# moana-lf-robot.net
KiCad netlist of a schematic drawn in EasyEDA
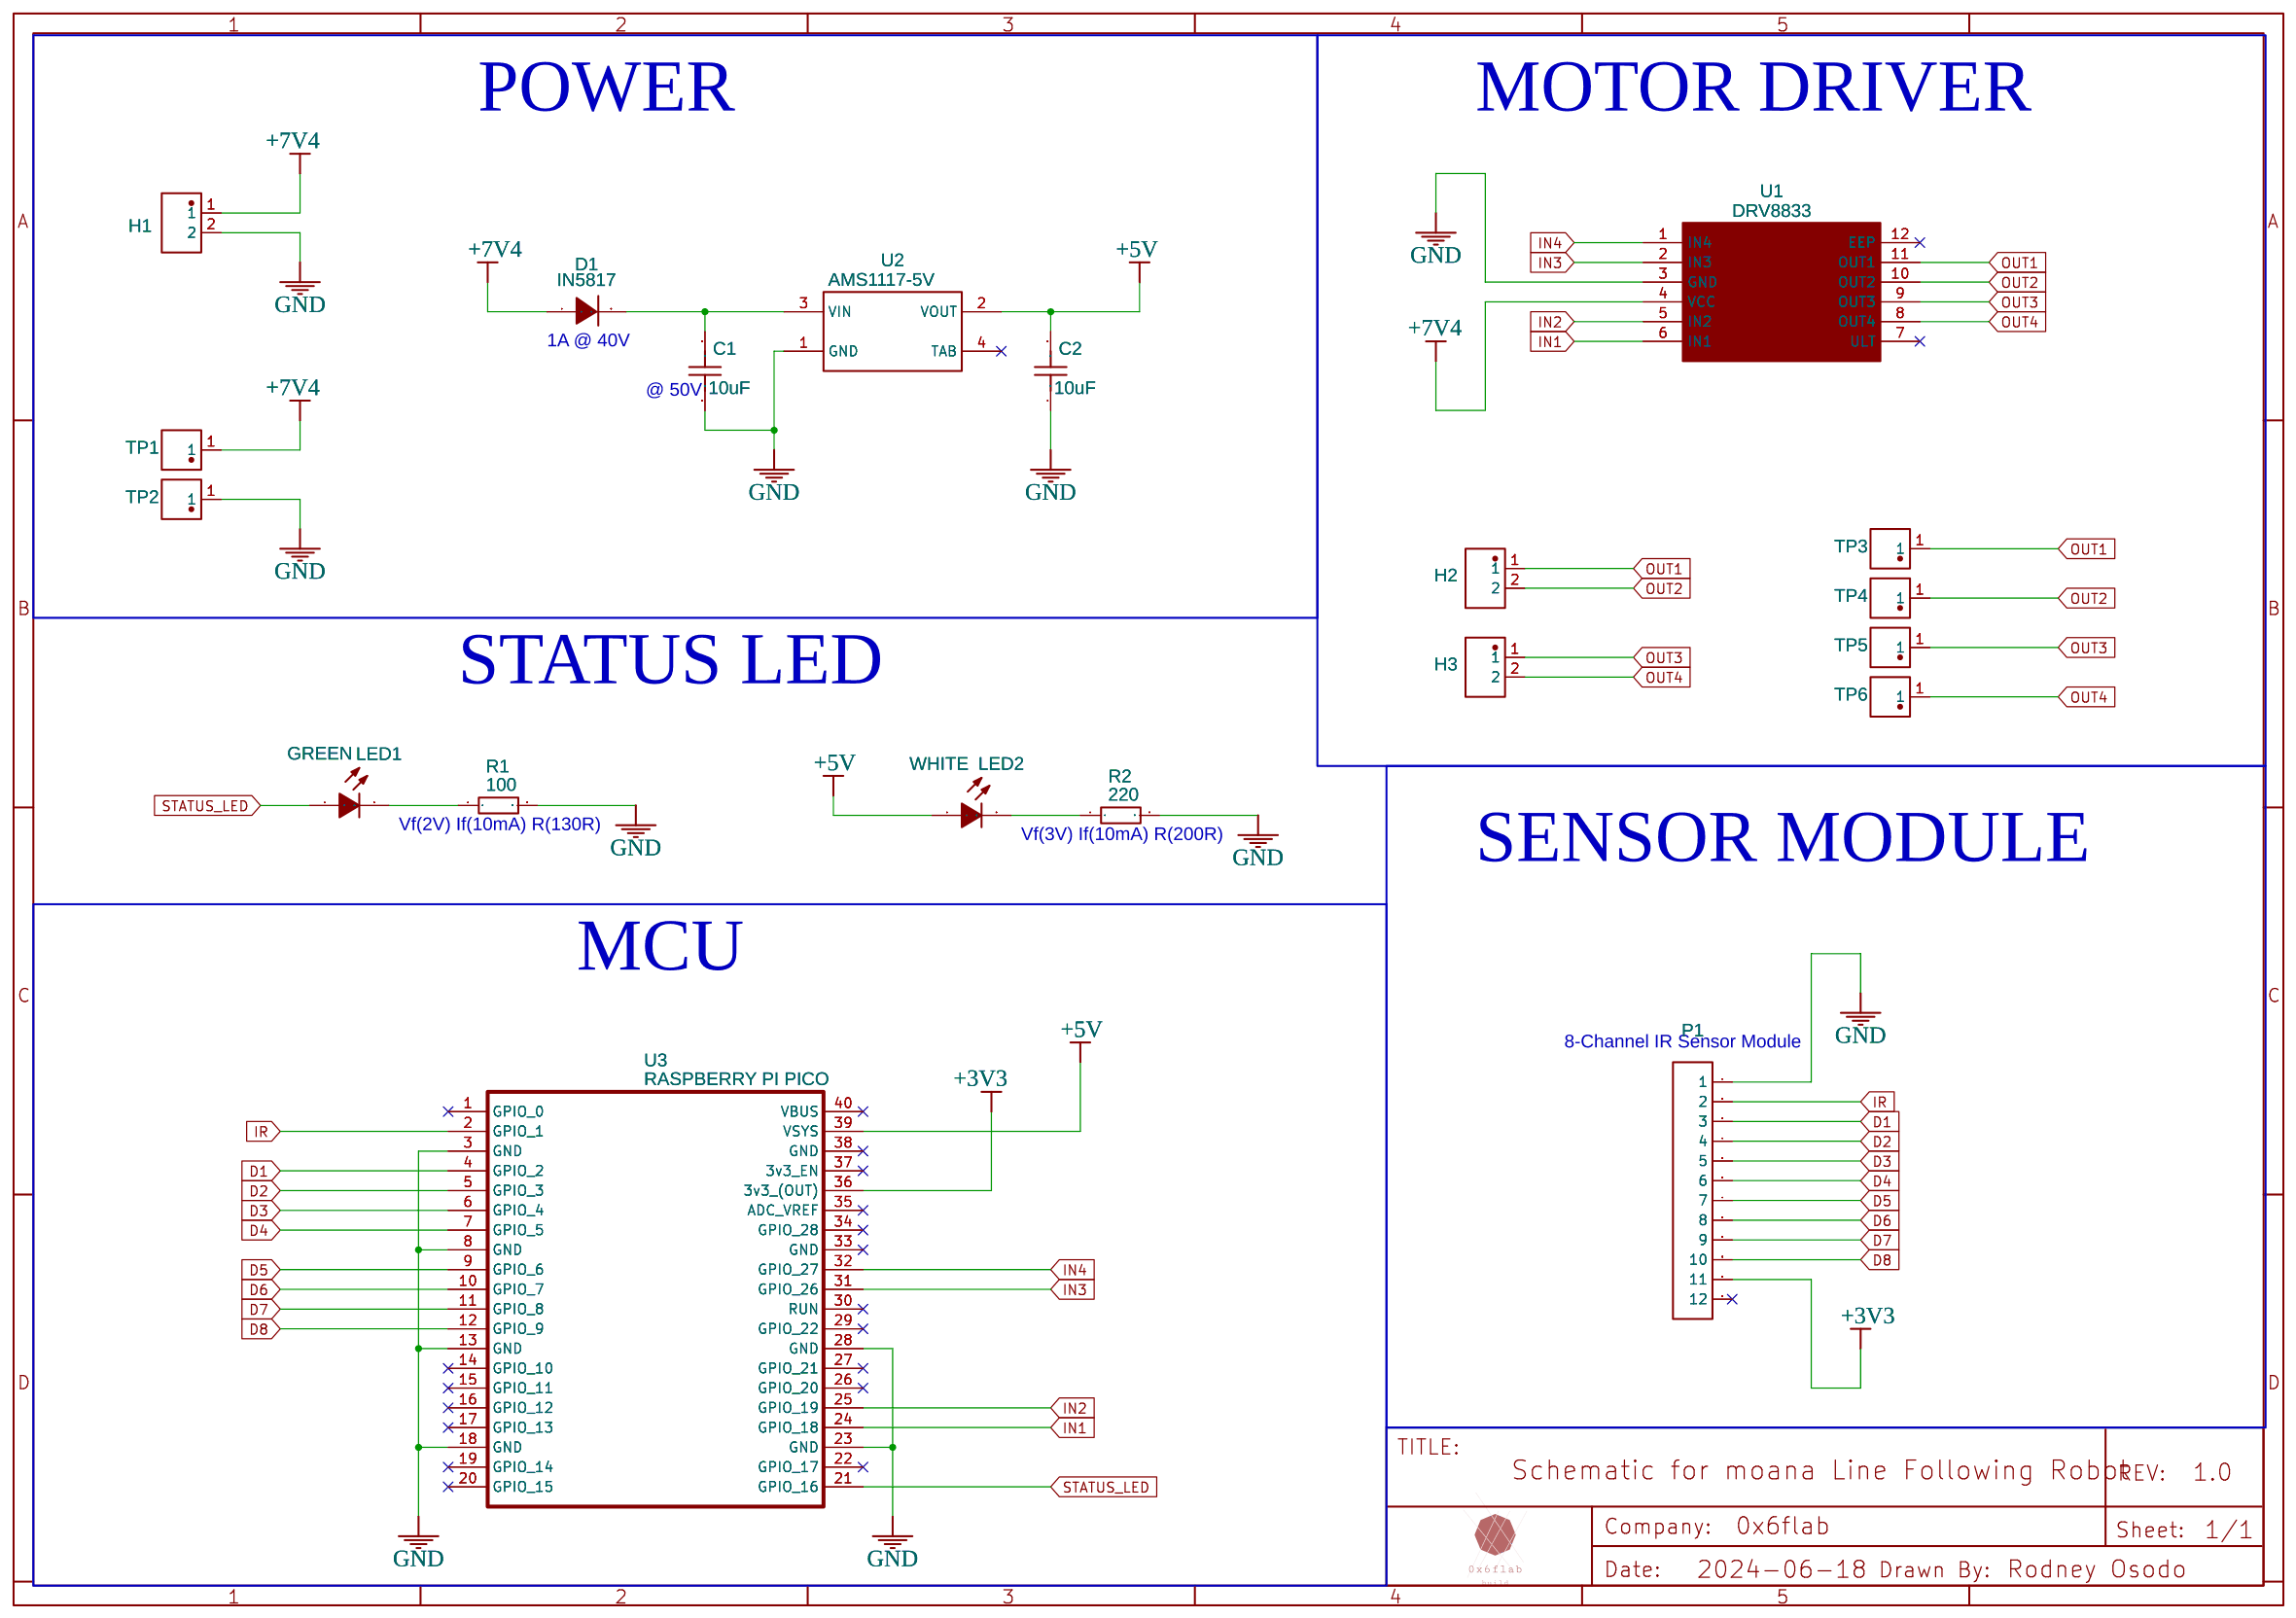
[diagram p0: schematic sheet]

(export (version "E")
  (design (tool "Eeschema 10.0.6"))
  (components
    (comp (ref "C1")
      (value "10uF")
      (fields
        (field (name "Manufacturer Part") "CC1H104ZC14D3F5O10MF")
        (field (name "Manufacturer") "Dersonic(德尔创)")
      )
      (libsource (lib "") (part "CC1H104ZC14D3F5O10MF"))
    )
    (comp (ref "C2")
      (value "10uF")
      (fields
        (field (name "Manufacturer Part") "CC1H104ZC14D3F5O10MF")
        (field (name "Manufacturer") "Dersonic(德尔创)")
      )
      (libsource (lib "") (part "CC1H104ZC14D3F5O10MF"))
    )
    (comp (ref "D1")
      (value "IN5817")
      (fields (field (name "Manufacturer Part") "1N5817") (field (name "Manufacturer") "STMicroelectronics"))
      (libsource (lib "") (part "IN5817 SCHOTTKY DIODE"))
    )
    (comp (ref "H1")
      (value "210-91-02GB01")
      (fields (field (name "Manufacturer") "PINREX(频锐科技)"))
      (libsource (lib "") (part "210-91-02GB01"))
    )
    (comp (ref "H2")
      (value "210-91-02GB01")
      (fields (field (name "Manufacturer") "PINREX(频锐科技)"))
      (libsource (lib "") (part "210-91-02GB01"))
    )
    (comp (ref "H3")
      (value "210-91-02GB01")
      (fields (field (name "Manufacturer") "PINREX(频锐科技)"))
      (libsource (lib "") (part "210-91-02GB01"))
    )
    (comp (ref "LED1")
      (value "GREEN")
      (fields
        (field (name "Manufacturer Part") "204-10SUBC/C470/S400-A4")
        (field (name "Manufacturer") "EVERLIGHT(亿光)")
      )
      (libsource (lib "") (part "204-10SUBC/C470/S400-A4"))
    )
    (comp (ref "LED2")
      (value "WHITE")
      (fields
        (field (name "Manufacturer Part") "204-10SUBC/C470/S400-A4")
        (field (name "Manufacturer") "EVERLIGHT(亿光)")
      )
      (libsource (lib "") (part "204-10SUBC/C470/S400-A4"))
    )
    (comp (ref "P1")
      (value "HEADER - 2.54MM 1X12")
      (fields (field (name "Manufacturer Part") "2.54_1x12") (field (name "Manufacturer") "ReliaPro"))
      (libsource (lib "") (part "HEADER - 2.54MM 1X12"))
    )
    (comp (ref "R1")
      (value "100")
      (fields (field (name "Manufacturer") "Chian Chia Elec"))
      (libsource (lib "") (part "MF1/4W-1Ω±1% T52"))
    )
    (comp (ref "R2")
      (value "220")
      (fields (field (name "Manufacturer") "Chian Chia Elec"))
      (libsource (lib "") (part "MF1/4W-1Ω±1% T52"))
    )
    (comp (ref "TP1")
      (value "TP_SMD_2.5mm")
      (fields (field (name "Manufacturer Part") "15X5焊片"))
      (libsource (lib "") (part "TP_SMD_2.5mm"))
    )
    (comp (ref "TP2")
      (value "TP_SMD_2.5mm")
      (fields (field (name "Manufacturer Part") "15X5焊片"))
      (libsource (lib "") (part "TP_SMD_2.5mm"))
    )
    (comp (ref "TP3")
      (value "TP_SMD_2.5mm")
      (fields (field (name "Manufacturer Part") "15X5焊片"))
      (libsource (lib "") (part "TP_SMD_2.5mm"))
    )
    (comp (ref "TP4")
      (value "TP_SMD_2.5mm")
      (fields (field (name "Manufacturer Part") "15X5焊片"))
      (libsource (lib "") (part "TP_SMD_2.5mm"))
    )
    (comp (ref "TP5")
      (value "TP_SMD_2.5mm")
      (fields (field (name "Manufacturer Part") "15X5焊片"))
      (libsource (lib "") (part "TP_SMD_2.5mm"))
    )
    (comp (ref "TP6")
      (value "TP_SMD_2.5mm")
      (fields (field (name "Manufacturer Part") "15X5焊片"))
      (libsource (lib "") (part "TP_SMD_2.5mm"))
    )
    (comp (ref "U1") (value "DRV8833") (libsource (lib "") (part "DRV8833")))
    (comp (ref "U2")
      (value "AMS1117-5V")
      (fields (field (name "Manufacturer") "WPMtek(维攀微)"))
      (libsource (lib "") (part "AMS1117-5V"))
    )
    (comp (ref "U3") (value "RASPBERRY PI PICO") (libsource (lib "") (part "RASPBERRY PI PICO")))
  )
  (nets
    (net (code "1") (name "+3V3") (class "Default")
      (node (ref "P1") (pin "11") (pinfunction "11_11") (pintype "input"))
      (node (ref "U3") (pin "36") (pinfunction "3v3_(OUT)_36") (pintype "unspecified"))
    )
    (net (code "2") (name "+5V") (class "Default")
      (node (ref "C2") (pin "2") (pinfunction "2_2") (pintype "unspecified"))
      (node (ref "LED2") (pin "1") (pinfunction "A_1") (pintype "input"))
      (node (ref "U2") (pin "2") (pinfunction "VOUT_2") (pintype "unspecified"))
      (node (ref "U3") (pin "39") (pinfunction "VSYS_39") (pintype "unspecified"))
    )
    (net (code "3") (name "+7V4") (class "Default")
      (node (ref "D1") (pin "1") (pinfunction "A_1") (pintype "unspecified"))
      (node (ref "H1") (pin "1") (pinfunction "1_1") (pintype "unspecified"))
      (node (ref "TP1") (pin "1") (pinfunction "1_1") (pintype "unspecified"))
      (node (ref "U1") (pin "4") (pinfunction "VCC_4") (pintype "unspecified"))
    )
    (net (code "4") (name "D1") (class "Default")
      (node (ref "P1") (pin "3") (pinfunction "3_3") (pintype "input"))
      (node (ref "U3") (pin "4") (pinfunction "GPIO_2_4") (pintype "unspecified"))
    )
    (net (code "5") (name "D2") (class "Default")
      (node (ref "P1") (pin "4") (pinfunction "4_4") (pintype "input"))
      (node (ref "U3") (pin "5") (pinfunction "GPIO_3_5") (pintype "unspecified"))
    )
    (net (code "6") (name "D3") (class "Default")
      (node (ref "P1") (pin "5") (pinfunction "5_5") (pintype "input"))
      (node (ref "U3") (pin "6") (pinfunction "GPIO_4_6") (pintype "unspecified"))
    )
    (net (code "7") (name "D4") (class "Default")
      (node (ref "P1") (pin "6") (pinfunction "6_6") (pintype "input"))
      (node (ref "U3") (pin "7") (pinfunction "GPIO_5_7") (pintype "unspecified"))
    )
    (net (code "8") (name "D5") (class "Default")
      (node (ref "P1") (pin "7") (pinfunction "7_7") (pintype "input"))
      (node (ref "U3") (pin "9") (pinfunction "GPIO_6_9") (pintype "unspecified"))
    )
    (net (code "9") (name "D6") (class "Default")
      (node (ref "P1") (pin "8") (pinfunction "8_8") (pintype "input"))
      (node (ref "U3") (pin "10") (pinfunction "GPIO_7_10") (pintype "unspecified"))
    )
    (net (code "10") (name "D7") (class "Default")
      (node (ref "P1") (pin "9") (pinfunction "9_9") (pintype "input"))
      (node (ref "U3") (pin "11") (pinfunction "GPIO_8_11") (pintype "unspecified"))
    )
    (net (code "11") (name "D8") (class "Default")
      (node (ref "P1") (pin "10") (pinfunction "10_10") (pintype "input"))
      (node (ref "U3") (pin "12") (pinfunction "GPIO_9_12") (pintype "unspecified"))
    )
    (net (code "12") (name "GND") (class "Default")
      (node (ref "C1") (pin "1") (pinfunction "1_1") (pintype "unspecified"))
      (node (ref "C2") (pin "1") (pinfunction "1_1") (pintype "unspecified"))
      (node (ref "H1") (pin "2") (pinfunction "2_2") (pintype "unspecified"))
      (node (ref "P1") (pin "1") (pinfunction "1_1") (pintype "input"))
      (node (ref "R1") (pin "2") (pinfunction "2_2") (pintype "unspecified"))
      (node (ref "R2") (pin "2") (pinfunction "2_2") (pintype "unspecified"))
      (node (ref "TP2") (pin "1") (pinfunction "1_1") (pintype "unspecified"))
      (node (ref "U1") (pin "3") (pinfunction "GND_3") (pintype "unspecified"))
      (node (ref "U2") (pin "1") (pinfunction "GND_1") (pintype "unspecified"))
      (node (ref "U3") (pin "13") (pinfunction "GND_13") (pintype "unspecified"))
      (node (ref "U3") (pin "18") (pinfunction "GND_18") (pintype "unspecified"))
      (node (ref "U3") (pin "23") (pinfunction "GND_23") (pintype "unspecified"))
      (node (ref "U3") (pin "28") (pinfunction "GND_28") (pintype "unspecified"))
      (node (ref "U3") (pin "3") (pinfunction "GND_3") (pintype "unspecified"))
      (node (ref "U3") (pin "8") (pinfunction "GND_8") (pintype "unspecified"))
    )
    (net (code "13") (name "IN1") (class "Default")
      (node (ref "U1") (pin "6") (pinfunction "IN1_6") (pintype "unspecified"))
      (node (ref "U3") (pin "24") (pinfunction "GPIO_18_24") (pintype "unspecified"))
    )
    (net (code "14") (name "IN2") (class "Default")
      (node (ref "U1") (pin "5") (pinfunction "IN2_5") (pintype "unspecified"))
      (node (ref "U3") (pin "25") (pinfunction "GPIO_19_25") (pintype "unspecified"))
    )
    (net (code "15") (name "IN3") (class "Default")
      (node (ref "U1") (pin "2") (pinfunction "IN3_2") (pintype "unspecified"))
      (node (ref "U3") (pin "31") (pinfunction "GPIO_26_31") (pintype "unspecified"))
    )
    (net (code "16") (name "IN4") (class "Default")
      (node (ref "U1") (pin "1") (pinfunction "IN4_1") (pintype "unspecified"))
      (node (ref "U3") (pin "32") (pinfunction "GPIO_27_32") (pintype "unspecified"))
    )
    (net (code "17") (name "IR") (class "Default")
      (node (ref "P1") (pin "2") (pinfunction "2_2") (pintype "input"))
      (node (ref "U3") (pin "2") (pinfunction "GPIO_1_2") (pintype "unspecified"))
    )
    (net (code "18") (name "Net-(D1-K)") (class "Default")
      (node (ref "C1") (pin "2") (pinfunction "2_2") (pintype "unspecified"))
      (node (ref "D1") (pin "2") (pinfunction "K_2") (pintype "unspecified"))
      (node (ref "U2") (pin "3") (pinfunction "VIN_3") (pintype "unspecified"))
    )
    (net (code "19") (name "Net-(LED1-C)") (class "Default")
      (node (ref "LED1") (pin "2") (pinfunction "C_2") (pintype "input"))
      (node (ref "R1") (pin "1") (pinfunction "1_1") (pintype "unspecified"))
    )
    (net (code "20") (name "Net-(LED2-C)") (class "Default")
      (node (ref "LED2") (pin "2") (pinfunction "C_2") (pintype "input"))
      (node (ref "R2") (pin "1") (pinfunction "1_1") (pintype "unspecified"))
    )
    (net (code "21") (name "OUT1") (class "Default")
      (node (ref "H2") (pin "1") (pinfunction "1_1") (pintype "unspecified"))
      (node (ref "TP3") (pin "1") (pinfunction "1_1") (pintype "unspecified"))
      (node (ref "U1") (pin "11") (pinfunction "OUT1_11") (pintype "unspecified"))
    )
    (net (code "22") (name "OUT2") (class "Default")
      (node (ref "H2") (pin "2") (pinfunction "2_2") (pintype "unspecified"))
      (node (ref "TP4") (pin "1") (pinfunction "1_1") (pintype "unspecified"))
      (node (ref "U1") (pin "10") (pinfunction "OUT2_10") (pintype "unspecified"))
    )
    (net (code "23") (name "OUT3") (class "Default")
      (node (ref "H3") (pin "1") (pinfunction "1_1") (pintype "unspecified"))
      (node (ref "TP5") (pin "1") (pinfunction "1_1") (pintype "unspecified"))
      (node (ref "U1") (pin "9") (pinfunction "OUT3_9") (pintype "unspecified"))
    )
    (net (code "24") (name "OUT4") (class "Default")
      (node (ref "H3") (pin "2") (pinfunction "2_2") (pintype "unspecified"))
      (node (ref "TP6") (pin "1") (pinfunction "1_1") (pintype "unspecified"))
      (node (ref "U1") (pin "8") (pinfunction "OUT4_8") (pintype "unspecified"))
    )
    (net (code "25") (name "STATUS_LED") (class "Default")
      (node (ref "LED1") (pin "1") (pinfunction "A_1") (pintype "input"))
      (node (ref "U3") (pin "21") (pinfunction "GPIO_16_21") (pintype "unspecified"))
    )
    (net (code "26") (name "unconnected-(P1-Pad12)") (class "Default")
      (node (ref "P1") (pin "12") (pinfunction "12_12") (pintype "input+no_connect"))
    )
    (net (code "27") (name "unconnected-(U1-EEP-Pad12)") (class "Default")
      (node (ref "U1") (pin "12") (pinfunction "EEP_12") (pintype "unspecified+no_connect"))
    )
    (net (code "28") (name "unconnected-(U1-ULT-Pad7)") (class "Default")
      (node (ref "U1") (pin "7") (pinfunction "ULT_7") (pintype "unspecified+no_connect"))
    )
    (net (code "29") (name "unconnected-(U2-TAB-Pad4)") (class "Default")
      (node (ref "U2") (pin "4") (pinfunction "TAB_4") (pintype "unspecified+no_connect"))
    )
    (net (code "30") (name "unconnected-(U3-3v3_EN-Pad37)") (class "Default")
      (node (ref "U3") (pin "37") (pinfunction "3v3_EN_37") (pintype "unspecified+no_connect"))
    )
    (net (code "31") (name "unconnected-(U3-ADC_VREF-Pad35)") (class "Default")
      (node (ref "U3") (pin "35") (pinfunction "ADC_VREF_35") (pintype "unspecified+no_connect"))
    )
    (net (code "32") (name "unconnected-(U3-GND-Pad33)") (class "Default")
      (node (ref "U3") (pin "33") (pinfunction "GND_33") (pintype "unspecified+no_connect"))
    )
    (net (code "33") (name "unconnected-(U3-GND-Pad38)") (class "Default")
      (node (ref "U3") (pin "38") (pinfunction "GND_38") (pintype "unspecified+no_connect"))
    )
    (net (code "34") (name "unconnected-(U3-GPIO_0-Pad1)") (class "Default")
      (node (ref "U3") (pin "1") (pinfunction "GPIO_0_1") (pintype "unspecified+no_connect"))
    )
    (net (code "35") (name "unconnected-(U3-GPIO_10-Pad14)") (class "Default")
      (node (ref "U3") (pin "14") (pinfunction "GPIO_10_14") (pintype "unspecified+no_connect"))
    )
    (net (code "36") (name "unconnected-(U3-GPIO_11-Pad15)") (class "Default")
      (node (ref "U3") (pin "15") (pinfunction "GPIO_11_15") (pintype "unspecified+no_connect"))
    )
    (net (code "37") (name "unconnected-(U3-GPIO_12-Pad16)") (class "Default")
      (node (ref "U3") (pin "16") (pinfunction "GPIO_12_16") (pintype "unspecified+no_connect"))
    )
    (net (code "38") (name "unconnected-(U3-GPIO_13-Pad17)") (class "Default")
      (node (ref "U3") (pin "17") (pinfunction "GPIO_13_17") (pintype "unspecified+no_connect"))
    )
    (net (code "39") (name "unconnected-(U3-GPIO_14-Pad19)") (class "Default")
      (node (ref "U3") (pin "19") (pinfunction "GPIO_14_19") (pintype "unspecified+no_connect"))
    )
    (net (code "40") (name "unconnected-(U3-GPIO_15-Pad20)") (class "Default")
      (node (ref "U3") (pin "20") (pinfunction "GPIO_15_20") (pintype "unspecified+no_connect"))
    )
    (net (code "41") (name "unconnected-(U3-GPIO_17-Pad22)") (class "Default")
      (node (ref "U3") (pin "22") (pinfunction "GPIO_17_22") (pintype "unspecified+no_connect"))
    )
    (net (code "42") (name "unconnected-(U3-GPIO_20-Pad26)") (class "Default")
      (node (ref "U3") (pin "26") (pinfunction "GPIO_20_26") (pintype "unspecified+no_connect"))
    )
    (net (code "43") (name "unconnected-(U3-GPIO_21-Pad27)") (class "Default")
      (node (ref "U3") (pin "27") (pinfunction "GPIO_21_27") (pintype "unspecified+no_connect"))
    )
    (net (code "44") (name "unconnected-(U3-GPIO_22-Pad29)") (class "Default")
      (node (ref "U3") (pin "29") (pinfunction "GPIO_22_29") (pintype "unspecified+no_connect"))
    )
    (net (code "45") (name "unconnected-(U3-GPIO_28-Pad34)") (class "Default")
      (node (ref "U3") (pin "34") (pinfunction "GPIO_28_34") (pintype "unspecified+no_connect"))
    )
    (net (code "46") (name "unconnected-(U3-RUN-Pad30)") (class "Default")
      (node (ref "U3") (pin "30") (pinfunction "RUN_30") (pintype "unspecified+no_connect"))
    )
    (net (code "47") (name "unconnected-(U3-VBUS-Pad40)") (class "Default")
      (node (ref "U3") (pin "40") (pinfunction "VBUS_40") (pintype "unspecified+no_connect"))
    )
  )
)
